# peripherals.net
KiCad netlist of a schematic drawn in Altium Designer
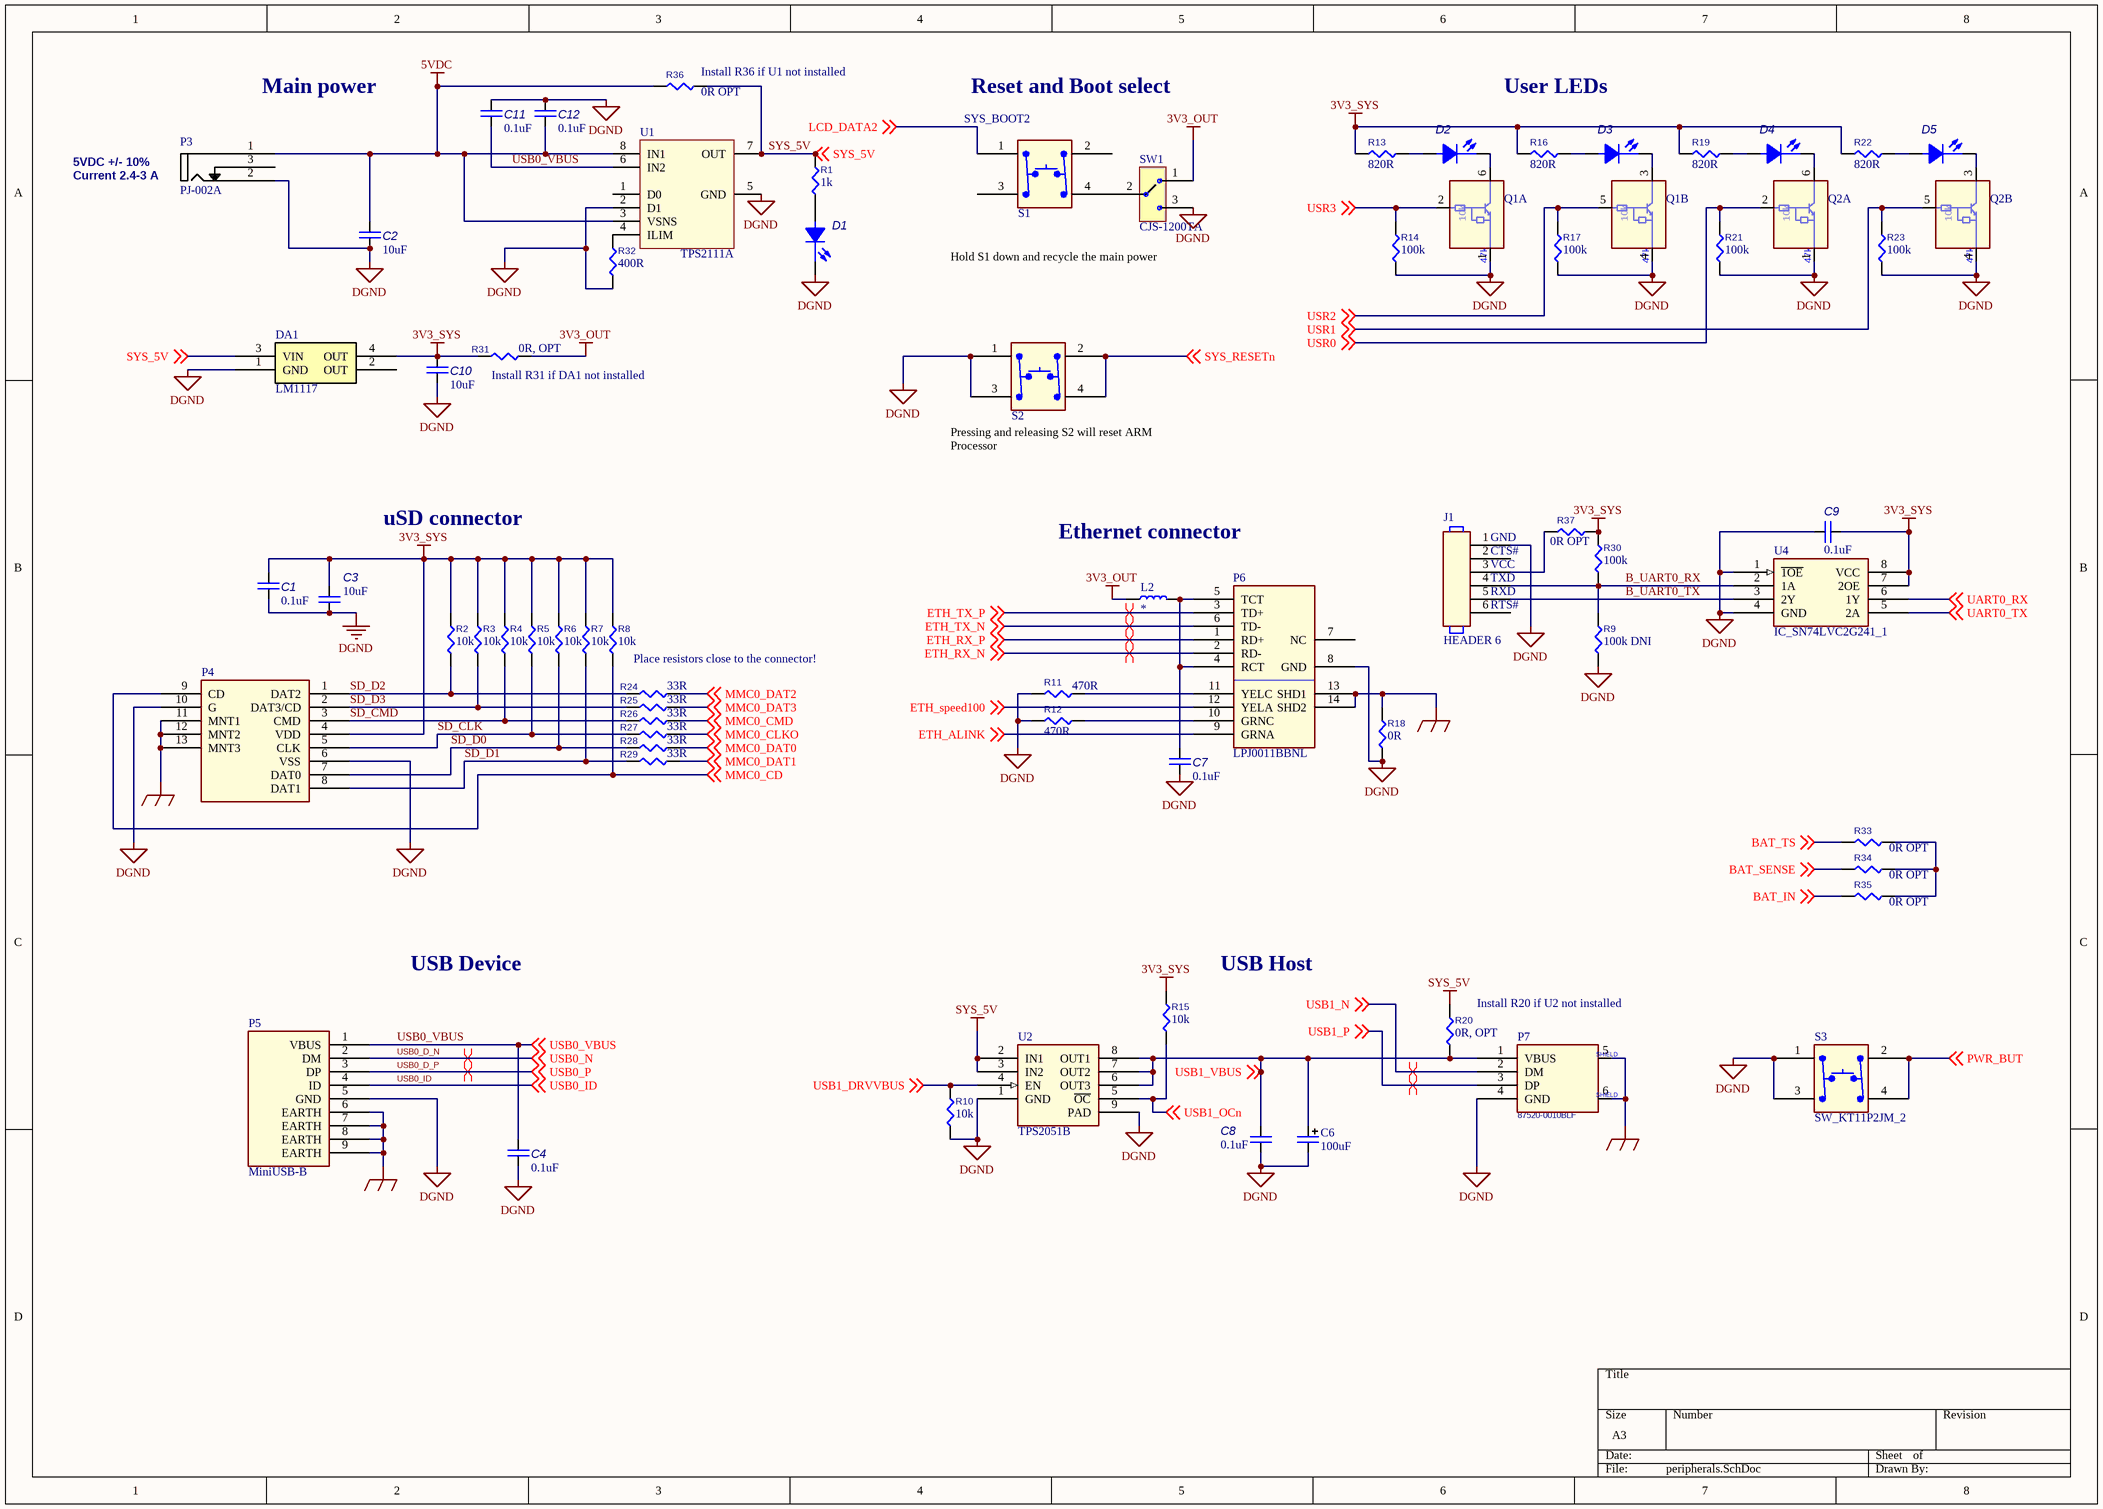
[diagram p0: peripherals.SchDoc]

(export (version "E")
  (design (tool "Eeschema 10.0.6"))
  (components
    (comp (ref "C1")
      (value "0.1uF")
      (footprint "CC1608-0603")
      (description "C0603")
      (libsource (lib "am335x-base") (part "C0603"))
    )
    (comp (ref "C2")
      (value "10uF")
      (footprint "CC2012-0805")
      (description "C0805")
      (libsource (lib "am335x-base") (part "C0805"))
    )
    (comp (ref "C3")
      (value "10uF")
      (footprint "CC2012-0805")
      (description "C0805")
      (libsource (lib "am335x-base") (part "C0805"))
    )
    (comp (ref "C4")
      (value "0.1uF")
      (footprint "CC1608-0603")
      (description "C0603")
      (libsource (lib "am335x-base") (part "C0603"))
    )
    (comp (ref "C6")
      (value "100uF")
      (footprint "Cap_C")
      (description "Tantalum Capacitor Case C")
      (fields (field (name "Comment") "Cap_C"))
      (libsource (lib "am335x-base") (part "Cap_C"))
    )
    (comp (ref "C7")
      (value "0.1uF")
      (footprint "CC1608-0603")
      (description "C0603")
      (libsource (lib "am335x-base") (part "C0603"))
    )
    (comp (ref "C8")
      (value "0.1uF")
      (footprint "CC1608-0603")
      (description "C0603")
      (libsource (lib "am335x-base") (part "C0603"))
    )
    (comp (ref "C9")
      (value "0.1uF")
      (footprint "CC1608-0603")
      (description "C0603")
      (libsource (lib "usomiq-base") (part "C0603"))
    )
    (comp (ref "C10")
      (value "10uF")
      (footprint "CC2012-0805")
      (description "C0805")
      (libsource (lib "am335x-base") (part "C0805"))
    )
    (comp (ref "C11")
      (value "0.1uF")
      (footprint "CC1608-0603")
      (description "C0603")
      (libsource (lib "am335x-base") (part "C0603"))
    )
    (comp (ref "C12")
      (value "0.1uF")
      (footprint "CC1608-0603")
      (description "C0603")
      (libsource (lib "am335x-base") (part "C0603"))
    )
    (comp (ref "D1")
      (value "LED0805")
      (footprint "LED0805")
      (description "LED 0805")
      (libsource (lib "am335x-base") (part "LED0805"))
    )
    (comp (ref "D2")
      (value "LED0805")
      (footprint "LED0805")
      (description "LED 0805")
      (libsource (lib "am335x-base") (part "LED0805"))
    )
    (comp (ref "D3")
      (value "LED0805")
      (footprint "LED0805")
      (description "LED 0805")
      (libsource (lib "am335x-base") (part "LED0805"))
    )
    (comp (ref "D4")
      (value "LED0805")
      (footprint "LED0805")
      (description "LED 0805")
      (libsource (lib "am335x-base") (part "LED0805"))
    )
    (comp (ref "D5")
      (value "LED0805")
      (footprint "LED0805")
      (description "LED 0805")
      (libsource (lib "am335x-base") (part "LED0805"))
    )
    (comp (ref "DA1")
      (value "LM1117")
      (footprint "SOT230P700X160-4N")
      (description "800mA Low-Dropout Linear Regulator")
      (fields (field (name "MANUFACTURER") "National"))
      (libsource (lib "usomiq-base") (part "LM1117"))
    )
    (comp (ref "J1")
      (value "HEADER 6")
      (footprint "DIP6")
      (description "CONN HEADER 6POS, VERTICAL,  .100 STR TIN")
      (fields (field (name "MFR") "FCI"))
      (libsource (lib "usomiq-base") (part "HEADER 6"))
    )
    (comp (ref "L2")
      (value "BLM18A-FB")
      (footprint "CHIP0603")
      (description "Chip EMIFILr Inductor Type")
      (fields (field (name "MANUFACTURER") "Murata") (field (name "MAN P/N") "*"))
      (libsource (lib "am335x-base") (part "BLM18A-FB"))
    )
    (comp (ref "P3")
      (value "PJ-002A")
      (footprint "PJ-002A")
      (description "DC POWER JACK")
      (fields (field (name "MANUFACTURER") "CIU Inc"))
      (libsource (lib "omap") (part "PJ-002A"))
    )
    (comp (ref "P4")
      (value "~")
      (footprint "TFC08WP01F-A-R1K-H")
      (description "Connector for microSD™ Card (Push-push Type)")
      (fields (field (name "MFR") "AUK Contractors Co, LTD"))
      (libsource (lib "usomiq-base") (part "TFC08WP01F-R1K-H-CN"))
    )
    (comp (ref "P5")
      (value "MiniUSB-B")
      (footprint "MINI-USB-B5 SMT")
      (description "Mini USB Type B CONNECTOR")
      (fields (field (name "MFR") "Hirose"))
      (libsource (lib "usomiq-base") (part "MiniUSB-B"))
    )
    (comp (ref "P6")
      (value "CONN_RJ45_MAG_WE_0")
      (footprint "TRJ0011ABNL")
      (description "RJ-45 10/100 W/Magnetics")
      (fields (field (name "MFR") "Link PP") (field (name "P/N") "LPJ0011BBNL"))
      (libsource (lib "am335x-base") (part "CONN_RJ45_MAG_WE_0"))
    )
    (comp (ref "P7")
      (value "CONN_54819-0578_2")
      (footprint "USB2.5-2H4C")
      (description "USB Type A Connectors")
      (fields (field (name "P/N") "87520-0010BLF") (field (name "MFR") "FCI"))
      (libsource (lib "am335x-base") (part "CONN_54819-0578_2"))
    )
    (comp (ref "Q1")
      (value "RN1907")
      (footprint "SOT363-6L")
      (description "Transistor Silicon NPN")
      (fields (field (name "MFR") "ONS"))
      (libsource (lib "usomiq-base") (part "RN1907"))
    )
    (comp (ref "Q2")
      (value "RN1907")
      (footprint "SOT363-6L")
      (description "Transistor Silicon NPN")
      (fields (field (name "MFR") "ONS"))
      (libsource (lib "usomiq-base") (part "RN1907"))
    )
    (comp (ref "R1")
      (value "1k")
      (footprint "RESC1608X55N")
      (description "R0603")
      (libsource (lib "am335x-base") (part "R0603"))
    )
    (comp (ref "R2")
      (value "10k")
      (footprint "RESC1608X55N")
      (description "R0603")
      (libsource (lib "am335x-base") (part "R0603"))
    )
    (comp (ref "R3")
      (value "10k")
      (footprint "RESC1608X55N")
      (description "R0603")
      (libsource (lib "am335x-base") (part "R0603"))
    )
    (comp (ref "R4")
      (value "10k")
      (footprint "RESC1608X55N")
      (description "R0603")
      (libsource (lib "am335x-base") (part "R0603"))
    )
    (comp (ref "R5")
      (value "10k")
      (footprint "RESC1608X55N")
      (description "R0603")
      (libsource (lib "am335x-base") (part "R0603"))
    )
    (comp (ref "R6")
      (value "10k")
      (footprint "RESC1608X55N")
      (description "R0603")
      (libsource (lib "am335x-base") (part "R0603"))
    )
    (comp (ref "R7")
      (value "10k")
      (footprint "RESC1608X55N")
      (description "R0603")
      (libsource (lib "am335x-base") (part "R0603"))
    )
    (comp (ref "R8")
      (value "10k")
      (footprint "RESC1608X55N")
      (description "R0603")
      (libsource (lib "am335x-base") (part "R0603"))
    )
    (comp (ref "R9")
      (value "100k DNI")
      (footprint "RESC1608X55N")
      (description "R0603")
      (libsource (lib "am335x-base") (part "R0603"))
    )
    (comp (ref "R10")
      (value "10k")
      (footprint "RESC1608X55N")
      (description "R0603")
      (libsource (lib "am335x-base") (part "R0603"))
    )
    (comp (ref "R11")
      (value "470R")
      (footprint "RESC1608X55N")
      (description "R0603")
      (libsource (lib "am335x-base") (part "R0603"))
    )
    (comp (ref "R12")
      (value "470R")
      (footprint "RESC1608X55N")
      (description "R0603")
      (libsource (lib "am335x-base") (part "R0603"))
    )
    (comp (ref "R13")
      (value "820R")
      (footprint "RESC1608X55N")
      (description "R0603")
      (libsource (lib "am335x-base") (part "R0603"))
    )
    (comp (ref "R14")
      (value "100k")
      (footprint "RESC1608X55N")
      (description "R0603")
      (libsource (lib "am335x-base") (part "R0603"))
    )
    (comp (ref "R15")
      (value "10k")
      (footprint "RESC1608X55N")
      (description "R0603")
      (libsource (lib "am335x-base") (part "R0603"))
    )
    (comp (ref "R16")
      (value "820R")
      (footprint "RESC1608X55N")
      (description "R0603")
      (libsource (lib "am335x-base") (part "R0603"))
    )
    (comp (ref "R17")
      (value "100k")
      (footprint "RESC1608X55N")
      (description "R0603")
      (libsource (lib "am335x-base") (part "R0603"))
    )
    (comp (ref "R18")
      (value "0R")
      (footprint "RESC1608X55N")
      (description "R0603")
      (libsource (lib "am335x-base") (part "R0603"))
    )
    (comp (ref "R19")
      (value "820R")
      (footprint "RESC1608X55N")
      (description "R0603")
      (libsource (lib "am335x-base") (part "R0603"))
    )
    (comp (ref "R20")
      (value "0R, OPT")
      (footprint "RESC1608X55N")
      (description "R0603")
      (libsource (lib "am335x-base") (part "R0603"))
    )
    (comp (ref "R21")
      (value "100k")
      (footprint "RESC1608X55N")
      (description "R0603")
      (libsource (lib "am335x-base") (part "R0603"))
    )
    (comp (ref "R22")
      (value "820R")
      (footprint "RESC1608X55N")
      (description "R0603")
      (libsource (lib "am335x-base") (part "R0603"))
    )
    (comp (ref "R23")
      (value "100k")
      (footprint "RESC1608X55N")
      (description "R0603")
      (libsource (lib "am335x-base") (part "R0603"))
    )
    (comp (ref "R24")
      (value "33R")
      (footprint "RESC1608X55N")
      (description "R0603")
      (libsource (lib "usomiq-base") (part "R0603"))
    )
    (comp (ref "R25")
      (value "33R")
      (footprint "RESC1608X55N")
      (description "R0603")
      (libsource (lib "usomiq-base") (part "R0603"))
    )
    (comp (ref "R26")
      (value "33R")
      (footprint "RESC1608X55N")
      (description "R0603")
      (libsource (lib "usomiq-base") (part "R0603"))
    )
    (comp (ref "R27")
      (value "33R")
      (footprint "RESC1608X55N")
      (description "R0603")
      (libsource (lib "usomiq-base") (part "R0603"))
    )
    (comp (ref "R28")
      (value "33R")
      (footprint "RESC1608X55N")
      (description "R0603")
      (libsource (lib "usomiq-base") (part "R0603"))
    )
    (comp (ref "R29")
      (value "33R")
      (footprint "RESC1608X55N")
      (description "R0603")
      (libsource (lib "usomiq-base") (part "R0603"))
    )
    (comp (ref "R30")
      (value "100k")
      (footprint "RESC1608X55N")
      (description "R0603")
      (libsource (lib "am335x-base") (part "R0603"))
    )
    (comp (ref "R31")
      (value "0R, OPT")
      (footprint "RESC1608X55N")
      (description "R0603")
      (libsource (lib "usomiq-base") (part "R0603"))
    )
    (comp (ref "R32")
      (value "400R")
      (footprint "RESC1608X55N")
      (description "R0603")
      (libsource (lib "usomiq-base") (part "R0603"))
    )
    (comp (ref "R33")
      (value "0R OPT")
      (footprint "RESC1608X55N")
      (description "R0603")
      (libsource (lib "usomiq-base") (part "R0603"))
    )
    (comp (ref "R34")
      (value "0R OPT")
      (footprint "RESC1608X55N")
      (description "R0603")
      (libsource (lib "usomiq-base") (part "R0603"))
    )
    (comp (ref "R35")
      (value "0R OPT")
      (footprint "RESC1608X55N")
      (description "R0603")
      (libsource (lib "usomiq-base") (part "R0603"))
    )
    (comp (ref "R36")
      (value "0R OPT")
      (footprint "RESC1608X55N")
      (description "R0603")
      (libsource (lib "usomiq-base") (part "R0603"))
    )
    (comp (ref "R37")
      (value "0R OPT")
      (footprint "RESC1608X55N")
      (description "R0603")
      (libsource (lib "usomiq-base") (part "R0603"))
    )
    (comp (ref "S1")
      (value "SW_KT11P2JM_2")
      (footprint "KMR231GLFS")
      (description "SMD button")
      (fields (field (name "MFR") "C&K Components"))
      (libsource (lib "usomiq-base") (part "SW_KT11P2JM_2"))
    )
    (comp (ref "S2")
      (value "SW_KT11P2JM_2")
      (footprint "KMR231GLFS")
      (description "SMD button")
      (fields (field (name "MFR") "C&K Components"))
      (libsource (lib "usomiq-base") (part "SW_KT11P2JM_2"))
    )
    (comp (ref "S3")
      (value "SW_KT11P2JM_2")
      (footprint "KMR231GLFS")
      (description "SMD button")
      (fields (field (name "MFR") "C&K Components"))
      (libsource (lib "usomiq-base") (part "SW_KT11P2JM_2"))
    )
    (comp (ref "SW1")
      (value "CJS-1200TA")
      (footprint "CJS-1200A1")
      (description "SWITCH SLIDE SPDT")
      (libsource (lib "usomiq-base") (part "CJS-1200TA"))
    )
    (comp (ref "U1")
      (value "TPS211xA")
      (footprint "TSSOP-8")
      (description "Single Channel, Current-Limited USB Power Distribution Switch")
      (fields (field (name "MANUFACTURER") "TI") (field (name "P/N") "TPS2111A"))
      (libsource (lib "usomiq-base") (part "TPS211xA"))
    )
    (comp (ref "U2")
      (value "TPS2051B")
      (footprint "R-PDSO-G8")
      (description "CURRENT-LIMITED, POWER-DISTRIBUTION SWITCHES")
      (fields (field (name "MFR") "TI"))
      (libsource (lib "usomiq-base") (part "TPS2051B"))
    )
    (comp (ref "U4")
      (value "IC_SN74LVC2G241_1")
      (footprint "SOP127P600-8N")
      (description "Dual Buffer/Driver With 3-State Outputs")
      (fields (field (name "MFR") "TI"))
      (libsource (lib "usomiq-base") (part "IC_SN74LVC2G241_1"))
    )
  )
  (nets
    (net (code "1") (name "/B_UART0_RX") (class "Default")
      (node (ref "J1") (pin "4") (pinfunction "4_4") (pintype "passive"))
      (node (ref "R30") (pin "1") (pinfunction "1_1") (pintype "passive"))
      (node (ref "R9") (pin "2") (pinfunction "2_2") (pintype "passive"))
      (node (ref "U4") (pin "2") (pinfunction "1A_2") (pintype "passive"))
    )
    (net (code "2") (name "/B_UART0_TX") (class "Default")
      (node (ref "J1") (pin "5") (pinfunction "5_5") (pintype "passive"))
      (node (ref "U4") (pin "3") (pinfunction "2Y_3") (pintype "passive"))
    )
    (net (code "3") (name "/SD_CLK") (class "Default")
      (node (ref "P4") (pin "5") (pinfunction "CLK_5") (pintype "passive"))
      (node (ref "R27") (pin "1") (pinfunction "1_1") (pintype "passive"))
      (node (ref "R5") (pin "1") (pinfunction "1_1") (pintype "passive"))
    )
    (net (code "4") (name "/SD_CMD") (class "Default")
      (node (ref "P4") (pin "3") (pinfunction "CMD_3") (pintype "passive"))
      (node (ref "R26") (pin "1") (pinfunction "1_1") (pintype "passive"))
      (node (ref "R4") (pin "1") (pinfunction "1_1") (pintype "passive"))
    )
    (net (code "5") (name "/SD_D0") (class "Default")
      (node (ref "P4") (pin "7") (pinfunction "DAT0_7") (pintype "passive"))
      (node (ref "R28") (pin "1") (pinfunction "1_1") (pintype "passive"))
      (node (ref "R6") (pin "1") (pinfunction "1_1") (pintype "passive"))
    )
    (net (code "6") (name "/SD_D1") (class "Default")
      (node (ref "P4") (pin "8") (pinfunction "DAT1_8") (pintype "passive"))
      (node (ref "R29") (pin "1") (pinfunction "1_1") (pintype "passive"))
      (node (ref "R7") (pin "1") (pinfunction "1_1") (pintype "passive"))
    )
    (net (code "7") (name "/SD_D2") (class "Default")
      (node (ref "P4") (pin "1") (pinfunction "DAT2_1") (pintype "passive"))
      (node (ref "R2") (pin "1") (pinfunction "1_1") (pintype "passive"))
      (node (ref "R24") (pin "1") (pinfunction "1_1") (pintype "passive"))
    )
    (net (code "8") (name "/SD_D3") (class "Default")
      (node (ref "P4") (pin "2") (pinfunction "DAT3/CD_2") (pintype "passive"))
      (node (ref "R25") (pin "1") (pinfunction "1_1") (pintype "passive"))
      (node (ref "R3") (pin "1") (pinfunction "1_1") (pintype "passive"))
    )
    (net (code "9") (name "3V3_OUT") (class "Default")
      (node (ref "L2") (pin "1") (pinfunction "1_1") (pintype "passive"))
      (node (ref "R31") (pin "2") (pinfunction "2_2") (pintype "passive"))
      (node (ref "SW1") (pin "1") (pinfunction "1_1") (pintype "passive"))
    )
    (net (code "10") (name "3V3_SYS") (class "Default")
      (node (ref "C1") (pin "1") (pinfunction "1_1") (pintype "passive"))
      (node (ref "C10") (pin "2") (pinfunction "2_2") (pintype "passive"))
      (node (ref "C3") (pin "2") (pinfunction "2_2") (pintype "passive"))
      (node (ref "C9") (pin "2") (pinfunction "2_2") (pintype "passive"))
      (node (ref "DA1") (pin "4") (pinfunction "OUT_4") (pintype "power_in"))
      (node (ref "P4") (pin "4") (pinfunction "VDD_4") (pintype "power_in"))
      (node (ref "R13") (pin "2") (pinfunction "2_2") (pintype "passive"))
      (node (ref "R15") (pin "2") (pinfunction "2_2") (pintype "passive"))
      (node (ref "R16") (pin "2") (pinfunction "2_2") (pintype "passive"))
      (node (ref "R19") (pin "2") (pinfunction "2_2") (pintype "passive"))
      (node (ref "R2") (pin "2") (pinfunction "2_2") (pintype "passive"))
      (node (ref "R22") (pin "2") (pinfunction "2_2") (pintype "passive"))
      (node (ref "R3") (pin "2") (pinfunction "2_2") (pintype "passive"))
      (node (ref "R30") (pin "2") (pinfunction "2_2") (pintype "passive"))
      (node (ref "R31") (pin "1") (pinfunction "1_1") (pintype "passive"))
      (node (ref "R37") (pin "2") (pinfunction "2_2") (pintype "passive"))
      (node (ref "R4") (pin "2") (pinfunction "2_2") (pintype "passive"))
      (node (ref "R5") (pin "2") (pinfunction "2_2") (pintype "passive"))
      (node (ref "R6") (pin "2") (pinfunction "2_2") (pintype "passive"))
      (node (ref "R7") (pin "2") (pinfunction "2_2") (pintype "passive"))
      (node (ref "R8") (pin "2") (pinfunction "2_2") (pintype "passive"))
      (node (ref "U4") (pin "7") (pinfunction "2OE_7") (pintype "passive"))
      (node (ref "U4") (pin "8") (pinfunction "VCC_8") (pintype "power_in"))
    )
    (net (code "11") (name "5VDC") (class "Default")
      (node (ref "C12") (pin "2") (pinfunction "2_2") (pintype "passive"))
      (node (ref "C2") (pin "2") (pinfunction "2_2") (pintype "passive"))
      (node (ref "P3") (pin "1") (pinfunction "GND_1") (pintype "passive"))
      (node (ref "R36") (pin "1") (pinfunction "1_1") (pintype "passive"))
      (node (ref "U1") (pin "3") (pinfunction "VSNS_3") (pintype "passive"))
      (node (ref "U1") (pin "8") (pinfunction "IN1_8") (pintype "passive"))
    )
    (net (code "12") (name "BAT_IN") (class "Default")
      (node (ref "R35") (pin "1") (pinfunction "1_1") (pintype "passive"))
    )
    (net (code "13") (name "BAT_SENSE") (class "Default")
      (node (ref "R34") (pin "1") (pinfunction "1_1") (pintype "passive"))
    )
    (net (code "14") (name "BAT_TS") (class "Default")
      (node (ref "R33") (pin "1") (pinfunction "1_1") (pintype "passive"))
    )
    (net (code "15") (name "DGND") (class "Default")
      (node (ref "C1") (pin "2") (pinfunction "2_2") (pintype "passive"))
      (node (ref "C10") (pin "1") (pinfunction "1_1") (pintype "passive"))
      (node (ref "C11") (pin "1") (pinfunction "1_1") (pintype "passive"))
      (node (ref "C12") (pin "1") (pinfunction "1_1") (pintype "passive"))
      (node (ref "C2") (pin "1") (pinfunction "1_1") (pintype "passive"))
      (node (ref "C3") (pin "1") (pinfunction "1_1") (pintype "passive"))
      (node (ref "C4") (pin "2") (pinfunction "2_2") (pintype "passive"))
      (node (ref "C6") (pin "2") (pinfunction "2_2") (pintype "passive"))
      (node (ref "C7") (pin "2") (pinfunction "2_2") (pintype "passive"))
      (node (ref "C8") (pin "1") (pinfunction "1_1") (pintype "passive"))
      (node (ref "C9") (pin "1") (pinfunction "1_1") (pintype "passive"))
      (node (ref "D1") (pin "2") (pinfunction "C_2") (pintype "passive"))
      (node (ref "DA1") (pin "1") (pinfunction "GND_1") (pintype "power_in"))
      (node (ref "J1") (pin "1") (pinfunction "1_1") (pintype "passive"))
      (node (ref "P3") (pin "2") (pinfunction "RIGHT_2") (pintype "passive"))
      (node (ref "P4") (pin "10") (pinfunction "G_10") (pintype "passive"))
      (node (ref "P4") (pin "6") (pinfunction "VSS_6") (pintype "power_in"))
      (node (ref "P5") (pin "5") (pinfunction "GND_5") (pintype "power_in"))
      (node (ref "P6") (pin "8") (pinfunction "GND_8") (pintype "passive"))
      (node (ref "P7") (pin "4") (pinfunction "GND_4") (pintype "passive"))
      (node (ref "Q1") (pin "1") (pinfunction "4_1") (pintype "passive"))
      (node (ref "Q1") (pin "4") (pinfunction "4_4") (pintype "passive"))
      (node (ref "Q2") (pin "1") (pinfunction "4_1") (pintype "passive"))
      (node (ref "Q2") (pin "4") (pinfunction "4_4") (pintype "passive"))
      (node (ref "R10") (pin "1") (pinfunction "1_1") (pintype "passive"))
      (node (ref "R11") (pin "1") (pinfunction "1_1") (pintype "passive"))
      (node (ref "R12") (pin "1") (pinfunction "1_1") (pintype "passive"))
      (node (ref "R14") (pin "1") (pinfunction "1_1") (pintype "passive"))
      (node (ref "R17") (pin "1") (pinfunction "1_1") (pintype "passive"))
      (node (ref "R18") (pin "1") (pinfunction "1_1") (pintype "passive"))
      (node (ref "R21") (pin "1") (pinfunction "1_1") (pintype "passive"))
      (node (ref "R23") (pin "1") (pinfunction "1_1") (pintype "passive"))
      (node (ref "R32") (pin "2") (pinfunction "2_2") (pintype "passive"))
      (node (ref "R9") (pin "1") (pinfunction "1_1") (pintype "passive"))
      (node (ref "S2") (pin "1") (pinfunction "A1_1") (pintype "passive"))
      (node (ref "S2") (pin "3") (pinfunction "A2_3") (pintype "passive"))
      (node (ref "S3") (pin "1") (pinfunction "A1_1") (pintype "passive"))
      (node (ref "S3") (pin "3") (pinfunction "A2_3") (pintype "passive"))
      (node (ref "SW1") (pin "3") (pinfunction "3_3") (pintype "passive"))
      (node (ref "U1") (pin "2") (pinfunction "D1_2") (pintype "passive"))
      (node (ref "U1") (pin "5") (pinfunction "GND_5") (pintype "passive"))
      (node (ref "U2") (pin "1") (pinfunction "GND_1") (pintype "power_in"))
      (node (ref "U2") (pin "9") (pinfunction "PAD_9") (pintype "passive"))
      (node (ref "U4") (pin "1") (pinfunction "~{1OE}_1") (pintype "input"))
      (node (ref "U4") (pin "4") (pinfunction "GND_4") (pintype "power_in"))
    )
    (net (code "16") (name "EARTH") (class "Default")
      (node (ref "P4") (pin "11") (pinfunction "MNT1_11") (pintype "passive"))
      (node (ref "P4") (pin "12") (pinfunction "MNT2_12") (pintype "passive"))
      (node (ref "P4") (pin "13") (pinfunction "MNT3_13") (pintype "passive"))
      (node (ref "P5") (pin "6") (pinfunction "EARTH_6") (pintype "passive"))
      (node (ref "P5") (pin "7") (pinfunction "EARTH_7") (pintype "passive"))
      (node (ref "P5") (pin "8") (pinfunction "EARTH_8") (pintype "passive"))
      (node (ref "P5") (pin "9") (pinfunction "EARTH_9") (pintype "passive"))
      (node (ref "P6") (pin "13") (pinfunction "SHD1_13") (pintype "passive"))
      (node (ref "P6") (pin "14") (pinfunction "SHD2_14") (pintype "passive"))
      (node (ref "P7") (pin "5") (pinfunction "SHELD1_5") (pintype "passive"))
      (node (ref "P7") (pin "6") (pinfunction "PAD4_6") (pintype "passive"))
      (node (ref "R18") (pin "2") (pinfunction "2_2") (pintype "passive"))
    )
    (net (code "17") (name "ETH_ALINK") (class "Default")
      (node (ref "P6") (pin "9") (pinfunction "GRNA_9") (pintype "passive"))
    )
    (net (code "18") (name "ETH_RX_N") (class "Default")
      (node (ref "P6") (pin "2") (pinfunction "RD-_2") (pintype "passive"))
    )
    (net (code "19") (name "ETH_RX_P") (class "Default")
      (node (ref "P6") (pin "1") (pinfunction "RD+_1") (pintype "passive"))
    )
    (net (code "20") (name "ETH_TX_N") (class "Default")
      (node (ref "P6") (pin "6") (pinfunction "TD-_6") (pintype "passive"))
    )
    (net (code "21") (name "ETH_TX_P") (class "Default")
      (node (ref "P6") (pin "3") (pinfunction "TD+_3") (pintype "passive"))
    )
    (net (code "22") (name "ETH_speed100") (class "Default")
      (node (ref "P6") (pin "12") (pinfunction "YELA_12") (pintype "passive"))
    )
    (net (code "23") (name "LCD_DATA2") (class "Default")
      (node (ref "S1") (pin "1") (pinfunction "A1_1") (pintype "passive"))
    )
    (net (code "24") (name "MMC0_CD") (class "Default")
      (node (ref "P4") (pin "9") (pinfunction "CD_9") (pintype "passive"))
      (node (ref "R8") (pin "1") (pinfunction "1_1") (pintype "passive"))
    )
    (net (code "25") (name "MMC0_CLKO") (class "Default")
      (node (ref "R27") (pin "2") (pinfunction "2_2") (pintype "passive"))
    )
    (net (code "26") (name "MMC0_CMD") (class "Default")
      (node (ref "R26") (pin "2") (pinfunction "2_2") (pintype "passive"))
    )
    (net (code "27") (name "MMC0_DAT0") (class "Default")
      (node (ref "R28") (pin "2") (pinfunction "2_2") (pintype "passive"))
    )
    (net (code "28") (name "MMC0_DAT1") (class "Default")
      (node (ref "R29") (pin "2") (pinfunction "2_2") (pintype "passive"))
    )
    (net (code "29") (name "MMC0_DAT2") (class "Default")
      (node (ref "R24") (pin "2") (pinfunction "2_2") (pintype "passive"))
    )
    (net (code "30") (name "MMC0_DAT3") (class "Default")
      (node (ref "R25") (pin "2") (pinfunction "2_2") (pintype "passive"))
    )
    (net (code "31") (name "Net-(D1-A)") (class "Default")
      (node (ref "D1") (pin "1") (pinfunction "A_1") (pintype "passive"))
      (node (ref "R1") (pin "1") (pinfunction "1_1") (pintype "passive"))
    )
    (net (code "32") (name "Net-(D2-A)") (class "Default")
      (node (ref "D2") (pin "1") (pinfunction "A_1") (pintype "passive"))
      (node (ref "R13") (pin "1") (pinfunction "1_1") (pintype "passive"))
    )
    (net (code "33") (name "Net-(D2-C)") (class "Default")
      (node (ref "D2") (pin "2") (pinfunction "C_2") (pintype "passive"))
      (node (ref "Q1") (pin "6") (pinfunction "3_6") (pintype "passive"))
    )
    (net (code "34") (name "Net-(D3-A)") (class "Default")
      (node (ref "D3") (pin "1") (pinfunction "A_1") (pintype "passive"))
      (node (ref "R16") (pin "1") (pinfunction "1_1") (pintype "passive"))
    )
    (net (code "35") (name "Net-(D3-C)") (class "Default")
      (node (ref "D3") (pin "2") (pinfunction "C_2") (pintype "passive"))
      (node (ref "Q1") (pin "3") (pinfunction "3_3") (pintype "passive"))
    )
    (net (code "36") (name "Net-(D4-A)") (class "Default")
      (node (ref "D4") (pin "1") (pinfunction "A_1") (pintype "passive"))
      (node (ref "R19") (pin "1") (pinfunction "1_1") (pintype "passive"))
    )
    (net (code "37") (name "Net-(D4-C)") (class "Default")
      (node (ref "D4") (pin "2") (pinfunction "C_2") (pintype "passive"))
      (node (ref "Q2") (pin "6") (pinfunction "3_6") (pintype "passive"))
    )
    (net (code "38") (name "Net-(D5-A)") (class "Default")
      (node (ref "D5") (pin "1") (pinfunction "A_1") (pintype "passive"))
      (node (ref "R22") (pin "1") (pinfunction "1_1") (pintype "passive"))
    )
    (net (code "39") (name "Net-(D5-C)") (class "Default")
      (node (ref "D5") (pin "2") (pinfunction "C_2") (pintype "passive"))
      (node (ref "Q2") (pin "3") (pinfunction "3_3") (pintype "passive"))
    )
    (net (code "40") (name "Net-(J1-Pad3)") (class "Default")
      (node (ref "J1") (pin "3") (pinfunction "3_3") (pintype "passive"))
      (node (ref "R37") (pin "1") (pinfunction "1_1") (pintype "passive"))
    )
    (net (code "41") (name "Net-(P6-GRNC)") (class "Default")
      (node (ref "P6") (pin "10") (pinfunction "GRNC_10") (pintype "passive"))
      (node (ref "R12") (pin "2") (pinfunction "2_2") (pintype "passive"))
    )
    (net (code "42") (name "Net-(P6-RCT)") (class "Default")
      (node (ref "C7") (pin "1") (pinfunction "1_1") (pintype "passive"))
      (node (ref "L2") (pin "2") (pinfunction "2_2") (pintype "passive"))
      (node (ref "P6") (pin "4") (pinfunction "RCT_4") (pintype "passive"))
      (node (ref "P6") (pin "5") (pinfunction "TCT_5") (pintype "passive"))
    )
    (net (code "43") (name "Net-(P6-YELC)") (class "Default")
      (node (ref "P6") (pin "11") (pinfunction "YELC_11") (pintype "passive"))
      (node (ref "R11") (pin "2") (pinfunction "2_2") (pintype "passive"))
    )
    (net (code "44") (name "Net-(R33-Pad2)") (class "Default")
      (node (ref "R33") (pin "2") (pinfunction "2_2") (pintype "passive"))
      (node (ref "R34") (pin "2") (pinfunction "2_2") (pintype "passive"))
      (node (ref "R35") (pin "2") (pinfunction "2_2") (pintype "passive"))
    )
    (net (code "45") (name "Net-(S1-B2)") (class "Default")
      (node (ref "S1") (pin "4") (pinfunction "B2_4") (pintype "passive"))
      (node (ref "SW1") (pin "2") (pinfunction "2_2") (pintype "passive"))
    )
    (net (code "46") (name "Net-(U1-ILIM)") (class "Default")
      (node (ref "R32") (pin "1") (pinfunction "1_1") (pintype "passive"))
      (node (ref "U1") (pin "4") (pinfunction "ILIM_4") (pintype "passive"))
    )
    (net (code "47") (name "PWR_BUT") (class "Default")
      (node (ref "S3") (pin "2") (pinfunction "B1_2") (pintype "passive"))
      (node (ref "S3") (pin "4") (pinfunction "B2_4") (pintype "passive"))
    )
    (net (code "48") (name "SYS_5V") (class "Default")
      (node (ref "DA1") (pin "3") (pinfunction "VIN_3") (pintype "power_in"))
      (node (ref "R1") (pin "2") (pinfunction "2_2") (pintype "passive"))
      (node (ref "R20") (pin "2") (pinfunction "2_2") (pintype "passive"))
      (node (ref "R36") (pin "2") (pinfunction "2_2") (pintype "passive"))
      (node (ref "U1") (pin "7") (pinfunction "OUT_7") (pintype "passive"))
      (node (ref "U2") (pin "2") (pinfunction "IN1_2") (pintype "power_in"))
      (node (ref "U2") (pin "3") (pinfunction "IN2_3") (pintype "power_in"))
    )
    (net (code "49") (name "SYS_RESETn") (class "Default")
      (node (ref "S2") (pin "2") (pinfunction "B1_2") (pintype "passive"))
      (node (ref "S2") (pin "4") (pinfunction "B2_4") (pintype "passive"))
    )
    (net (code "50") (name "UART0_RX") (class "Default")
      (node (ref "U4") (pin "6") (pinfunction "1Y_6") (pintype "passive"))
    )
    (net (code "51") (name "UART0_TX") (class "Default")
      (node (ref "U4") (pin "5") (pinfunction "2A_5") (pintype "passive"))
    )
    (net (code "52") (name "USB0_ID") (class "Default")
      (node (ref "P5") (pin "4") (pinfunction "ID_4") (pintype "passive"))
    )
    (net (code "53") (name "USB0_N") (class "Default")
      (node (ref "P5") (pin "2") (pinfunction "DM_2") (pintype "passive"))
    )
    (net (code "54") (name "USB0_P") (class "Default")
      (node (ref "P5") (pin "3") (pinfunction "DP_3") (pintype "passive"))
    )
    (net (code "55") (name "USB0_VBUS") (class "Default")
      (node (ref "C11") (pin "2") (pinfunction "2_2") (pintype "passive"))
      (node (ref "C4") (pin "1") (pinfunction "1_1") (pintype "passive"))
      (node (ref "P5") (pin "1") (pinfunction "VBUS_1") (pintype "power_in"))
      (node (ref "U1") (pin "6") (pinfunction "IN2_6") (pintype "passive"))
    )
    (net (code "56") (name "USB1_DRVVBUS") (class "Default")
      (node (ref "R10") (pin "2") (pinfunction "2_2") (pintype "passive"))
      (node (ref "U2") (pin "4") (pinfunction "EN_4") (pintype "input"))
    )
    (net (code "57") (name "USB1_N") (class "Default")
      (node (ref "P7") (pin "2") (pinfunction "DM_2") (pintype "passive"))
    )
    (net (code "58") (name "USB1_OCn") (class "Default")
      (node (ref "R15") (pin "1") (pinfunction "1_1") (pintype "passive"))
      (node (ref "U2") (pin "5") (pinfunction "~{OC}_5") (pintype "passive"))
    )
    (net (code "59") (name "USB1_P") (class "Default")
      (node (ref "P7") (pin "3") (pinfunction "DP_3") (pintype "passive"))
    )
    (net (code "60") (name "USB1_VBUS") (class "Default")
      (node (ref "C6") (pin "1") (pinfunction "1_1") (pintype "passive"))
      (node (ref "C8") (pin "2") (pinfunction "2_2") (pintype "passive"))
      (node (ref "P7") (pin "1") (pinfunction "VBUS_1") (pintype "passive"))
      (node (ref "R20") (pin "1") (pinfunction "1_1") (pintype "passive"))
      (node (ref "U2") (pin "6") (pinfunction "OUT3_6") (pintype "power_in"))
      (node (ref "U2") (pin "7") (pinfunction "OUT2_7") (pintype "power_in"))
      (node (ref "U2") (pin "8") (pinfunction "OUT1_8") (pintype "power_in"))
    )
    (net (code "61") (name "USR0") (class "Default")
      (node (ref "Q2") (pin "2") (pinfunction "5_2") (pintype "passive"))
      (node (ref "R21") (pin "2") (pinfunction "2_2") (pintype "passive"))
    )
    (net (code "62") (name "USR1") (class "Default")
      (node (ref "Q2") (pin "5") (pinfunction "5_5") (pintype "passive"))
      (node (ref "R23") (pin "2") (pinfunction "2_2") (pintype "passive"))
    )
    (net (code "63") (name "USR2") (class "Default")
      (node (ref "Q1") (pin "5") (pinfunction "5_5") (pintype "passive"))
      (node (ref "R17") (pin "2") (pinfunction "2_2") (pintype "passive"))
    )
    (net (code "64") (name "USR3") (class "Default")
      (node (ref "Q1") (pin "2") (pinfunction "5_2") (pintype "passive"))
      (node (ref "R14") (pin "2") (pinfunction "2_2") (pintype "passive"))
    )
    (net (code "65") (name "unconnected-(DA1-OUT-Pad2)") (class "Default")
      (node (ref "DA1") (pin "2") (pinfunction "OUT_2") (pintype "power_in"))
    )
    (net (code "66") (name "unconnected-(J1-Pad2)") (class "Default")
      (node (ref "J1") (pin "2") (pinfunction "2_2") (pintype "passive"))
    )
    (net (code "67") (name "unconnected-(J1-Pad6)") (class "Default")
      (node (ref "J1") (pin "6") (pinfunction "6_6") (pintype "passive"))
    )
    (net (code "68") (name "unconnected-(P3-LEFT-Pad3)") (class "Default")
      (node (ref "P3") (pin "3") (pinfunction "LEFT_3") (pintype "passive"))
    )
    (net (code "69") (name "unconnected-(P6-NC-Pad7)") (class "Default")
      (node (ref "P6") (pin "7") (pinfunction "NC_7") (pintype "passive"))
    )
    (net (code "70") (name "unconnected-(S1-A2-Pad3)") (class "Default")
      (node (ref "S1") (pin "3") (pinfunction "A2_3") (pintype "passive"))
    )
    (net (code "71") (name "unconnected-(S1-B1-Pad2)") (class "Default")
      (node (ref "S1") (pin "2") (pinfunction "B1_2") (pintype "passive"))
    )
    (net (code "72") (name "unconnected-(U1-D0-Pad1)") (class "Default")
      (node (ref "U1") (pin "1") (pinfunction "D0_1") (pintype "passive"))
    )
  )
)
